# T02_LED_Cube.net
KiCad netlist of a schematic drawn in EAGLE
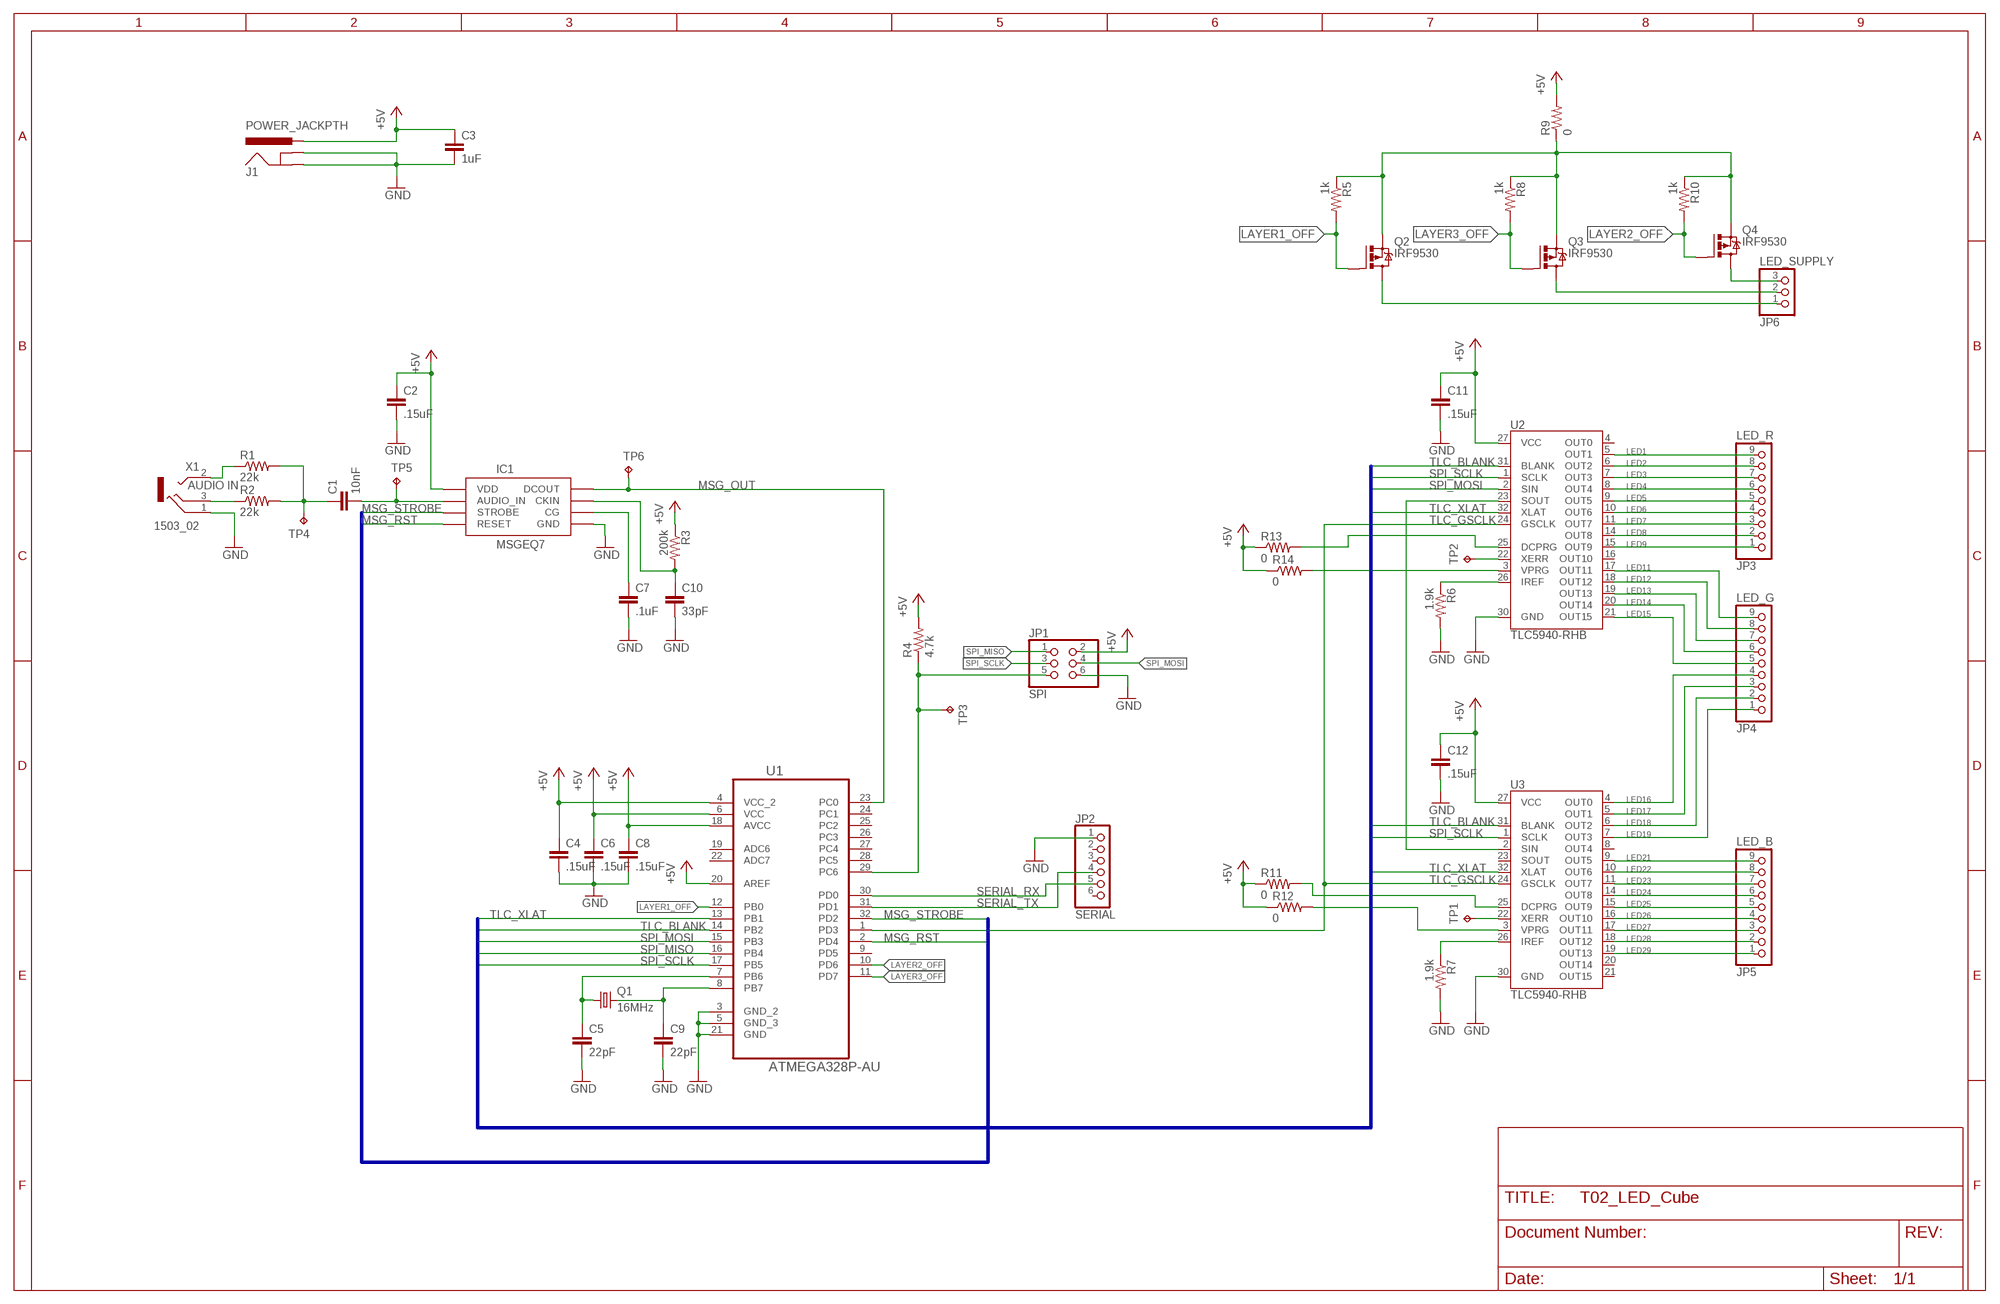
[diagram p0: schematic, sheet 1]

(export (version "E")
  (design (tool "Eeschema 10.0.6"))
  (components
    (comp (ref "C1")
      (value "10nF")
      (footprint "eagle-import:C0805")
      (libsource (lib "eagle-import") (part "C-EUC0805"))
    )
    (comp (ref "C2")
      (value ".15uF")
      (footprint "eagle-import:C0402")
      (libsource (lib "eagle-import") (part "C-EUC0402"))
    )
    (comp (ref "C3")
      (value "1uF")
      (footprint "eagle-import:C0805")
      (libsource (lib "eagle-import") (part "C-EUC0805"))
    )
    (comp (ref "C4")
      (value ".15uF")
      (footprint "eagle-import:C0402")
      (libsource (lib "eagle-import") (part "C-EUC0402"))
    )
    (comp (ref "C5")
      (value "22pF")
      (footprint "eagle-import:C0805")
      (libsource (lib "eagle-import") (part "C-EUC0805"))
    )
    (comp (ref "C6")
      (value ".15uF")
      (footprint "eagle-import:C0402")
      (libsource (lib "eagle-import") (part "C-EUC0402"))
    )
    (comp (ref "C7")
      (value ".1uF")
      (footprint "eagle-import:C0805")
      (libsource (lib "eagle-import") (part "C-EUC0805"))
    )
    (comp (ref "C8")
      (value ".15uF")
      (footprint "eagle-import:C0402")
      (libsource (lib "eagle-import") (part "C-EUC0402"))
    )
    (comp (ref "C9")
      (value "22pF")
      (footprint "eagle-import:C0805")
      (libsource (lib "eagle-import") (part "C-EUC0805"))
    )
    (comp (ref "C10")
      (value "33pF")
      (footprint "eagle-import:C0805")
      (libsource (lib "eagle-import") (part "C-EUC0805"))
    )
    (comp (ref "C11")
      (value ".15uF")
      (footprint "eagle-import:C0402")
      (libsource (lib "eagle-import") (part "C-EUC0402"))
    )
    (comp (ref "C12")
      (value ".15uF")
      (footprint "eagle-import:C0402")
      (libsource (lib "eagle-import") (part "C-EUC0402"))
    )
    (comp (ref "IC1")
      (value "MSGEQ7SOIC")
      (footprint "eagle-import:SOIC8")
      (libsource (lib "eagle-import") (part "MSGEQ7SOIC"))
    )
    (comp (ref "J1")
      (value "POWER_JACKPTH")
      (footprint "eagle-import:POWER_JACK_PTH")
      (libsource (lib "eagle-import") (part "POWER_JACKPTH"))
    )
    (comp (ref "JP1")
      (value "SPI")
      (footprint "eagle-import:2X03")
      (libsource (lib "eagle-import") (part "PINHD-2X3"))
    )
    (comp (ref "JP2")
      (value "SERIAL")
      (footprint "eagle-import:1X06")
      (libsource (lib "eagle-import") (part "PINHD-1X6"))
    )
    (comp (ref "JP3")
      (value "LED_R")
      (footprint "eagle-import:1X09")
      (libsource (lib "eagle-import") (part "PINHD-1X9"))
    )
    (comp (ref "JP4")
      (value "LED_G")
      (footprint "eagle-import:1X09")
      (libsource (lib "eagle-import") (part "PINHD-1X9"))
    )
    (comp (ref "JP5")
      (value "LED_B")
      (footprint "eagle-import:1X09")
      (libsource (lib "eagle-import") (part "PINHD-1X9"))
    )
    (comp (ref "JP6")
      (value "LED_SUPPLY")
      (footprint "eagle-import:1X03")
      (libsource (lib "eagle-import") (part "PINHD-1X3"))
    )
    (comp (ref "Q1")
      (value "16MHz")
      (footprint "eagle-import:HC49UP")
      (libsource (lib "eagle-import") (part "CRYSTALHC49UP"))
    )
    (comp (ref "Q2")
      (value "IRF9530")
      (footprint "eagle-import:TO220BV")
      (libsource (lib "eagle-import") (part "IRF9530"))
    )
    (comp (ref "Q3")
      (value "IRF9530")
      (footprint "eagle-import:TO220BV")
      (libsource (lib "eagle-import") (part "IRF9530"))
    )
    (comp (ref "Q4")
      (value "IRF9530")
      (footprint "eagle-import:TO220BV")
      (libsource (lib "eagle-import") (part "IRF9530"))
    )
    (comp (ref "R1")
      (value "22k")
      (footprint "eagle-import:R0805")
      (libsource (lib "eagle-import") (part "R-US_R0805"))
    )
    (comp (ref "R2")
      (value "22k")
      (footprint "eagle-import:R0805")
      (libsource (lib "eagle-import") (part "R-US_R0805"))
    )
    (comp (ref "R3")
      (value "200k")
      (footprint "eagle-import:R0805")
      (libsource (lib "eagle-import") (part "R-US_R0805"))
    )
    (comp (ref "R4")
      (value "4.7k")
      (footprint "eagle-import:R0805")
      (libsource (lib "eagle-import") (part "R-US_R0805"))
    )
    (comp (ref "R5")
      (value "1k")
      (footprint "eagle-import:R0805")
      (libsource (lib "eagle-import") (part "R-US_R0805"))
    )
    (comp (ref "R6")
      (value "1.9k")
      (footprint "eagle-import:R0402")
      (libsource (lib "eagle-import") (part "R-US_R0402"))
    )
    (comp (ref "R7")
      (value "1.9k")
      (footprint "eagle-import:R0402")
      (libsource (lib "eagle-import") (part "R-US_R0402"))
    )
    (comp (ref "R8")
      (value "1k")
      (footprint "eagle-import:R0805")
      (libsource (lib "eagle-import") (part "R-US_R0805"))
    )
    (comp (ref "R9")
      (value "0")
      (footprint "eagle-import:R1210")
      (libsource (lib "eagle-import") (part "R-US_R1210"))
    )
    (comp (ref "R10")
      (value "1k")
      (footprint "eagle-import:R0805")
      (libsource (lib "eagle-import") (part "R-US_R0805"))
    )
    (comp (ref "R11")
      (value "0")
      (footprint "eagle-import:R0402")
      (libsource (lib "eagle-import") (part "R-US_R0402"))
    )
    (comp (ref "R12")
      (value "0")
      (footprint "eagle-import:R0402")
      (libsource (lib "eagle-import") (part "R-US_R0402"))
    )
    (comp (ref "R13")
      (value "0")
      (footprint "eagle-import:R0402")
      (libsource (lib "eagle-import") (part "R-US_R0402"))
    )
    (comp (ref "R14")
      (value "0")
      (footprint "eagle-import:R0402")
      (libsource (lib "eagle-import") (part "R-US_R0402"))
    )
    (comp (ref "TP1")
      (value "TPPAD1-13")
      (footprint "eagle-import:P1-13")
      (libsource (lib "eagle-import") (part "TPPAD1-13"))
    )
    (comp (ref "TP2")
      (value "TPPAD1-13")
      (footprint "eagle-import:P1-13")
      (libsource (lib "eagle-import") (part "TPPAD1-13"))
    )
    (comp (ref "TP3")
      (value "TPPAD1-13")
      (footprint "eagle-import:P1-13")
      (libsource (lib "eagle-import") (part "TPPAD1-13"))
    )
    (comp (ref "TP4")
      (value "TPPAD1-13")
      (footprint "eagle-import:P1-13")
      (libsource (lib "eagle-import") (part "TPPAD1-13"))
    )
    (comp (ref "TP5")
      (value "TPPAD1-13")
      (footprint "eagle-import:P1-13")
      (libsource (lib "eagle-import") (part "TPPAD1-13"))
    )
    (comp (ref "TP6")
      (value "TPPAD1-13")
      (footprint "eagle-import:P1-13")
      (libsource (lib "eagle-import") (part "TPPAD1-13"))
    )
    (comp (ref "U1")
      (value "ATMEGA328P-AU")
      (footprint "eagle-import:QFP80P900X900X120-32N")
      (libsource (lib "eagle-import") (part "ATMEGA328P-AU"))
    )
    (comp (ref "U2")
      (value "TLC5940-RHB")
      (footprint "eagle-import:QFN-32")
      (libsource (lib "eagle-import") (part "TLC5940-RHB"))
    )
    (comp (ref "U3")
      (value "TLC5940-RHB")
      (footprint "eagle-import:QFN-32")
      (libsource (lib "eagle-import") (part "TLC5940-RHB"))
    )
    (comp (ref "X1")
      (value "1503_02")
      (footprint "eagle-import:1503_02")
      (libsource (lib "eagle-import") (part "1503_02"))
    )
  )
  (nets
    (net (code "1") (name "+5V") (class "Default")
      (node (ref "C11") (pin "1") (pinfunction "1_1") (pintype "passive"))
      (node (ref "C12") (pin "1") (pinfunction "1_1") (pintype "passive"))
      (node (ref "C2") (pin "1") (pinfunction "1_1") (pintype "passive"))
      (node (ref "C3") (pin "1") (pinfunction "1_1") (pintype "passive"))
      (node (ref "C4") (pin "1") (pinfunction "1_1") (pintype "passive"))
      (node (ref "C6") (pin "1") (pinfunction "1_1") (pintype "passive"))
      (node (ref "C8") (pin "1") (pinfunction "1_1") (pintype "passive"))
      (node (ref "IC1") (pin "1") (pinfunction "VDD_1") (pintype "input"))
      (node (ref "J1") (pin "PWR") (pinfunction "PWR_PWR") (pintype "bidirectional"))
      (node (ref "JP1") (pin "2") (pinfunction "2_2") (pintype "passive"))
      (node (ref "R11") (pin "1") (pinfunction "1_1") (pintype "passive"))
      (node (ref "R12") (pin "1") (pinfunction "1_1") (pintype "passive"))
      (node (ref "R13") (pin "1") (pinfunction "1_1") (pintype "passive"))
      (node (ref "R14") (pin "1") (pinfunction "1_1") (pintype "passive"))
      (node (ref "R3") (pin "1") (pinfunction "1_1") (pintype "passive"))
      (node (ref "R4") (pin "2") (pinfunction "2_2") (pintype "passive"))
      (node (ref "R9") (pin "2") (pinfunction "2_2") (pintype "passive"))
      (node (ref "U1") (pin "18") (pinfunction "AVCC_18") (pintype "power_in"))
      (node (ref "U1") (pin "20") (pinfunction "AREF_20") (pintype "input"))
      (node (ref "U1") (pin "4") (pinfunction "VCC_2_4") (pintype "power_in"))
      (node (ref "U1") (pin "6") (pinfunction "VCC_6") (pintype "power_in"))
      (node (ref "U2") (pin "27") (pinfunction "VCC_27") (pintype "bidirectional"))
      (node (ref "U3") (pin "27") (pinfunction "VCC_27") (pintype "bidirectional"))
    )
    (net (code "2") (name "/LED1") (class "Default")
      (node (ref "JP3") (pin "9") (pinfunction "9_9") (pintype "passive"))
      (node (ref "U2") (pin "5") (pinfunction "OUT1_5") (pintype "bidirectional"))
    )
    (net (code "3") (name "/LED2") (class "Default")
      (node (ref "JP3") (pin "8") (pinfunction "8_8") (pintype "passive"))
      (node (ref "U2") (pin "6") (pinfunction "OUT2_6") (pintype "bidirectional"))
    )
    (net (code "4") (name "/LED3") (class "Default")
      (node (ref "JP3") (pin "7") (pinfunction "7_7") (pintype "passive"))
      (node (ref "U2") (pin "7") (pinfunction "OUT3_7") (pintype "bidirectional"))
    )
    (net (code "5") (name "/LED4") (class "Default")
      (node (ref "JP3") (pin "6") (pinfunction "6_6") (pintype "passive"))
      (node (ref "U2") (pin "8") (pinfunction "OUT4_8") (pintype "bidirectional"))
    )
    (net (code "6") (name "/LED5") (class "Default")
      (node (ref "JP3") (pin "5") (pinfunction "5_5") (pintype "passive"))
      (node (ref "U2") (pin "9") (pinfunction "OUT5_9") (pintype "bidirectional"))
    )
    (net (code "7") (name "/LED6") (class "Default")
      (node (ref "JP3") (pin "4") (pinfunction "4_4") (pintype "passive"))
      (node (ref "U2") (pin "10") (pinfunction "OUT6_10") (pintype "bidirectional"))
    )
    (net (code "8") (name "/LED7") (class "Default")
      (node (ref "JP3") (pin "3") (pinfunction "3_3") (pintype "passive"))
      (node (ref "U2") (pin "11") (pinfunction "OUT7_11") (pintype "bidirectional"))
    )
    (net (code "9") (name "/LED8") (class "Default")
      (node (ref "JP3") (pin "2") (pinfunction "2_2") (pintype "passive"))
      (node (ref "U2") (pin "14") (pinfunction "OUT8_14") (pintype "bidirectional"))
    )
    (net (code "10") (name "/LED9") (class "Default")
      (node (ref "JP3") (pin "1") (pinfunction "1_1") (pintype "passive"))
      (node (ref "U2") (pin "15") (pinfunction "OUT9_15") (pintype "bidirectional"))
    )
    (net (code "11") (name "/LED11") (class "Default")
      (node (ref "JP4") (pin "9") (pinfunction "9_9") (pintype "passive"))
      (node (ref "U2") (pin "17") (pinfunction "OUT11_17") (pintype "bidirectional"))
    )
    (net (code "12") (name "/LED12") (class "Default")
      (node (ref "JP4") (pin "8") (pinfunction "8_8") (pintype "passive"))
      (node (ref "U2") (pin "18") (pinfunction "OUT12_18") (pintype "bidirectional"))
    )
    (net (code "13") (name "/LED13") (class "Default")
      (node (ref "JP4") (pin "7") (pinfunction "7_7") (pintype "passive"))
      (node (ref "U2") (pin "19") (pinfunction "OUT13_19") (pintype "bidirectional"))
    )
    (net (code "14") (name "/LED14") (class "Default")
      (node (ref "JP4") (pin "6") (pinfunction "6_6") (pintype "passive"))
      (node (ref "U2") (pin "20") (pinfunction "OUT14_20") (pintype "bidirectional"))
    )
    (net (code "15") (name "/LED15") (class "Default")
      (node (ref "JP4") (pin "5") (pinfunction "5_5") (pintype "passive"))
      (node (ref "U2") (pin "21") (pinfunction "OUT15_21") (pintype "bidirectional"))
    )
    (net (code "16") (name "/LED16") (class "Default")
      (node (ref "JP4") (pin "4") (pinfunction "4_4") (pintype "passive"))
      (node (ref "U3") (pin "4") (pinfunction "OUT0_4") (pintype "bidirectional"))
    )
    (net (code "17") (name "/LED17") (class "Default")
      (node (ref "JP4") (pin "3") (pinfunction "3_3") (pintype "passive"))
      (node (ref "U3") (pin "5") (pinfunction "OUT1_5") (pintype "bidirectional"))
    )
    (net (code "18") (name "/LED18") (class "Default")
      (node (ref "JP4") (pin "2") (pinfunction "2_2") (pintype "passive"))
      (node (ref "U3") (pin "6") (pinfunction "OUT2_6") (pintype "bidirectional"))
    )
    (net (code "19") (name "/LED19") (class "Default")
      (node (ref "JP4") (pin "1") (pinfunction "1_1") (pintype "passive"))
      (node (ref "U3") (pin "7") (pinfunction "OUT3_7") (pintype "bidirectional"))
    )
    (net (code "20") (name "/LED21") (class "Default")
      (node (ref "JP5") (pin "9") (pinfunction "9_9") (pintype "passive"))
      (node (ref "U3") (pin "9") (pinfunction "OUT5_9") (pintype "bidirectional"))
    )
    (net (code "21") (name "/LED22") (class "Default")
      (node (ref "JP5") (pin "8") (pinfunction "8_8") (pintype "passive"))
      (node (ref "U3") (pin "10") (pinfunction "OUT6_10") (pintype "bidirectional"))
    )
    (net (code "22") (name "/LED23") (class "Default")
      (node (ref "JP5") (pin "7") (pinfunction "7_7") (pintype "passive"))
      (node (ref "U3") (pin "11") (pinfunction "OUT7_11") (pintype "bidirectional"))
    )
    (net (code "23") (name "/LED24") (class "Default")
      (node (ref "JP5") (pin "6") (pinfunction "6_6") (pintype "passive"))
      (node (ref "U3") (pin "14") (pinfunction "OUT8_14") (pintype "bidirectional"))
    )
    (net (code "24") (name "/LED25") (class "Default")
      (node (ref "JP5") (pin "5") (pinfunction "5_5") (pintype "passive"))
      (node (ref "U3") (pin "15") (pinfunction "OUT9_15") (pintype "bidirectional"))
    )
    (net (code "25") (name "/LED26") (class "Default")
      (node (ref "JP5") (pin "4") (pinfunction "4_4") (pintype "passive"))
      (node (ref "U3") (pin "16") (pinfunction "OUT10_16") (pintype "bidirectional"))
    )
    (net (code "26") (name "/LED27") (class "Default")
      (node (ref "JP5") (pin "3") (pinfunction "3_3") (pintype "passive"))
      (node (ref "U3") (pin "17") (pinfunction "OUT11_17") (pintype "bidirectional"))
    )
    (net (code "27") (name "/LED28") (class "Default")
      (node (ref "JP5") (pin "2") (pinfunction "2_2") (pintype "passive"))
      (node (ref "U3") (pin "18") (pinfunction "OUT12_18") (pintype "bidirectional"))
    )
    (net (code "28") (name "/LED29") (class "Default")
      (node (ref "JP5") (pin "1") (pinfunction "1_1") (pintype "passive"))
      (node (ref "U3") (pin "19") (pinfunction "OUT13_19") (pintype "bidirectional"))
    )
    (net (code "29") (name "/MSG_OUT") (class "Default")
      (node (ref "IC1") (pin "3") (pinfunction "DCOUT_3") (pintype "bidirectional"))
      (node (ref "TP6") (pin "TP") (pinfunction "TP_TP") (pintype "input"))
      (node (ref "U1") (pin "23") (pinfunction "PC0_23") (pintype "bidirectional"))
    )
    (net (code "30") (name "/MSG_RST") (class "Default")
      (node (ref "IC1") (pin "7") (pinfunction "RESET_7") (pintype "input"))
      (node (ref "U1") (pin "2") (pinfunction "PD4_2") (pintype "bidirectional"))
    )
    (net (code "31") (name "/MSG_STROBE") (class "Default")
      (node (ref "IC1") (pin "4") (pinfunction "STROBE_4") (pintype "input"))
      (node (ref "U1") (pin "32") (pinfunction "PD2_32") (pintype "bidirectional"))
    )
    (net (code "32") (name "/SERIAL_RX") (class "Default")
      (node (ref "JP2") (pin "5") (pinfunction "5_5") (pintype "passive"))
      (node (ref "U1") (pin "30") (pinfunction "PD0_30") (pintype "bidirectional"))
    )
    (net (code "33") (name "/SERIAL_TX") (class "Default")
      (node (ref "JP2") (pin "4") (pinfunction "4_4") (pintype "passive"))
      (node (ref "U1") (pin "31") (pinfunction "PD1_31") (pintype "bidirectional"))
    )
    (net (code "34") (name "/TLC_BLANK") (class "Default")
      (node (ref "U1") (pin "14") (pinfunction "PB2_14") (pintype "bidirectional"))
      (node (ref "U2") (pin "31") (pinfunction "BLANK_31") (pintype "bidirectional"))
      (node (ref "U3") (pin "31") (pinfunction "BLANK_31") (pintype "bidirectional"))
    )
    (net (code "35") (name "/TLC_GSCLK") (class "Default")
      (node (ref "U1") (pin "1") (pinfunction "PD3_1") (pintype "bidirectional"))
      (node (ref "U2") (pin "24") (pinfunction "GSCLK_24") (pintype "bidirectional"))
      (node (ref "U3") (pin "24") (pinfunction "GSCLK_24") (pintype "bidirectional"))
    )
    (net (code "36") (name "/TLC_XLAT") (class "Default")
      (node (ref "U1") (pin "13") (pinfunction "PB1_13") (pintype "bidirectional"))
      (node (ref "U2") (pin "32") (pinfunction "XLAT_32") (pintype "bidirectional"))
      (node (ref "U3") (pin "32") (pinfunction "XLAT_32") (pintype "bidirectional"))
    )
    (net (code "37") (name "GND") (class "Default")
      (node (ref "C10") (pin "2") (pinfunction "2_2") (pintype "passive"))
      (node (ref "C11") (pin "2") (pinfunction "2_2") (pintype "passive"))
      (node (ref "C12") (pin "2") (pinfunction "2_2") (pintype "passive"))
      (node (ref "C2") (pin "2") (pinfunction "2_2") (pintype "passive"))
      (node (ref "C3") (pin "2") (pinfunction "2_2") (pintype "passive"))
      (node (ref "C4") (pin "2") (pinfunction "2_2") (pintype "passive"))
      (node (ref "C5") (pin "2") (pinfunction "2_2") (pintype "passive"))
      (node (ref "C6") (pin "2") (pinfunction "2_2") (pintype "passive"))
      (node (ref "C7") (pin "2") (pinfunction "2_2") (pintype "passive"))
      (node (ref "C8") (pin "2") (pinfunction "2_2") (pintype "passive"))
      (node (ref "C9") (pin "2") (pinfunction "2_2") (pintype "passive"))
      (node (ref "IC1") (pin "2") (pinfunction "GND_2") (pintype "bidirectional"))
      (node (ref "J1") (pin "GND") (pinfunction "GND_GND") (pintype "bidirectional"))
      (node (ref "J1") (pin "GNDBREAK") (pinfunction "GNDBREAK_GNDBREAK") (pintype "bidirectional"))
      (node (ref "JP1") (pin "6") (pinfunction "6_6") (pintype "passive"))
      (node (ref "JP2") (pin "1") (pinfunction "1_1") (pintype "passive"))
      (node (ref "R6") (pin "2") (pinfunction "2_2") (pintype "passive"))
      (node (ref "R7") (pin "2") (pinfunction "2_2") (pintype "passive"))
      (node (ref "U1") (pin "21") (pinfunction "GND_21") (pintype "passive"))
      (node (ref "U1") (pin "3") (pinfunction "GND_2_3") (pintype "passive"))
      (node (ref "U1") (pin "5") (pinfunction "GND_3_5") (pintype "passive"))
      (node (ref "U2") (pin "30") (pinfunction "GND_30") (pintype "bidirectional"))
      (node (ref "U3") (pin "30") (pinfunction "GND_30") (pintype "bidirectional"))
      (node (ref "X1") (pin "1") (pinfunction "1_1") (pintype "passive"))
    )
    (net (code "38") (name "LAYER1_OFF") (class "Default")
      (node (ref "Q2") (pin "G") (pinfunction "G_G") (pintype "passive"))
      (node (ref "R5") (pin "2") (pinfunction "2_2") (pintype "passive"))
      (node (ref "U1") (pin "12") (pinfunction "PB0_12") (pintype "bidirectional"))
    )
    (net (code "39") (name "LAYER2_OFF") (class "Default")
      (node (ref "Q4") (pin "G") (pinfunction "G_G") (pintype "passive"))
      (node (ref "R10") (pin "2") (pinfunction "2_2") (pintype "passive"))
      (node (ref "U1") (pin "10") (pinfunction "PD6_10") (pintype "bidirectional"))
    )
    (net (code "40") (name "LAYER3_OFF") (class "Default")
      (node (ref "Q3") (pin "G") (pinfunction "G_G") (pintype "passive"))
      (node (ref "R8") (pin "2") (pinfunction "2_2") (pintype "passive"))
      (node (ref "U1") (pin "11") (pinfunction "PD7_11") (pintype "bidirectional"))
    )
    (net (code "41") (name "Net-(C1-Pad1)") (class "Default")
      (node (ref "C1") (pin "1") (pinfunction "1_1") (pintype "passive"))
      (node (ref "R1") (pin "2") (pinfunction "2_2") (pintype "passive"))
      (node (ref "R2") (pin "2") (pinfunction "2_2") (pintype "passive"))
      (node (ref "TP4") (pin "TP") (pinfunction "TP_TP") (pintype "input"))
    )
    (net (code "42") (name "Net-(IC1-AUDIO_IN)") (class "Default")
      (node (ref "C1") (pin "2") (pinfunction "2_2") (pintype "passive"))
      (node (ref "IC1") (pin "5") (pinfunction "AUDIO_IN_5") (pintype "input"))
      (node (ref "TP5") (pin "TP") (pinfunction "TP_TP") (pintype "input"))
    )
    (net (code "43") (name "Net-(IC1-CG)") (class "Default")
      (node (ref "C7") (pin "1") (pinfunction "1_1") (pintype "passive"))
      (node (ref "IC1") (pin "6") (pinfunction "CG_6") (pintype "bidirectional"))
    )
    (net (code "44") (name "Net-(IC1-CKIN)") (class "Default")
      (node (ref "C10") (pin "1") (pinfunction "1_1") (pintype "passive"))
      (node (ref "IC1") (pin "8") (pinfunction "CKIN_8") (pintype "bidirectional"))
      (node (ref "R3") (pin "2") (pinfunction "2_2") (pintype "passive"))
    )
    (net (code "45") (name "Net-(JP6-Pad1)") (class "Default")
      (node (ref "JP6") (pin "1") (pinfunction "1_1") (pintype "passive"))
      (node (ref "Q2") (pin "D") (pinfunction "D_D") (pintype "passive"))
    )
    (net (code "46") (name "Net-(JP6-Pad2)") (class "Default")
      (node (ref "JP6") (pin "2") (pinfunction "2_2") (pintype "passive"))
      (node (ref "Q3") (pin "D") (pinfunction "D_D") (pintype "passive"))
    )
    (net (code "47") (name "Net-(JP6-Pad3)") (class "Default")
      (node (ref "JP6") (pin "3") (pinfunction "3_3") (pintype "passive"))
      (node (ref "Q4") (pin "D") (pinfunction "D_D") (pintype "passive"))
    )
    (net (code "48") (name "Net-(Q2-PadS)") (class "Default")
      (node (ref "Q2") (pin "S") (pinfunction "S_S") (pintype "passive"))
      (node (ref "Q3") (pin "S") (pinfunction "S_S") (pintype "passive"))
      (node (ref "Q4") (pin "S") (pinfunction "S_S") (pintype "passive"))
      (node (ref "R10") (pin "1") (pinfunction "1_1") (pintype "passive"))
      (node (ref "R5") (pin "1") (pinfunction "1_1") (pintype "passive"))
      (node (ref "R8") (pin "1") (pinfunction "1_1") (pintype "passive"))
      (node (ref "R9") (pin "1") (pinfunction "1_1") (pintype "passive"))
    )
    (net (code "49") (name "Net-(R1-Pad1)") (class "Default")
      (node (ref "R1") (pin "1") (pinfunction "1_1") (pintype "passive"))
      (node (ref "X1") (pin "2") (pinfunction "2_2") (pintype "passive"))
    )
    (net (code "50") (name "Net-(R2-Pad1)") (class "Default")
      (node (ref "R2") (pin "1") (pinfunction "1_1") (pintype "passive"))
      (node (ref "X1") (pin "3") (pinfunction "3_3") (pintype "passive"))
    )
    (net (code "51") (name "Net-(U1-PB6)") (class "Default")
      (node (ref "C5") (pin "1") (pinfunction "1_1") (pintype "passive"))
      (node (ref "Q1") (pin "1") (pinfunction "1_1") (pintype "passive"))
      (node (ref "U1") (pin "7") (pinfunction "PB6_7") (pintype "bidirectional"))
    )
    (net (code "52") (name "Net-(U1-PB7)") (class "Default")
      (node (ref "C9") (pin "1") (pinfunction "1_1") (pintype "passive"))
      (node (ref "Q1") (pin "2") (pinfunction "2_2") (pintype "passive"))
      (node (ref "U1") (pin "8") (pinfunction "PB7_8") (pintype "bidirectional"))
    )
    (net (code "53") (name "Net-(U1-PC6)") (class "Default")
      (node (ref "JP1") (pin "5") (pinfunction "5_5") (pintype "passive"))
      (node (ref "R4") (pin "1") (pinfunction "1_1") (pintype "passive"))
      (node (ref "TP3") (pin "TP") (pinfunction "TP_TP") (pintype "input"))
      (node (ref "U1") (pin "29") (pinfunction "PC6_29") (pintype "bidirectional"))
    )
    (net (code "54") (name "Net-(U2-DCPRG)") (class "Default")
      (node (ref "R13") (pin "2") (pinfunction "2_2") (pintype "passive"))
      (node (ref "U2") (pin "25") (pinfunction "DCPRG_25") (pintype "bidirectional"))
    )
    (net (code "55") (name "Net-(U2-IREF)") (class "Default")
      (node (ref "R6") (pin "1") (pinfunction "1_1") (pintype "passive"))
      (node (ref "U2") (pin "26") (pinfunction "IREF_26") (pintype "bidirectional"))
    )
    (net (code "56") (name "Net-(U2-SOUT)") (class "Default")
      (node (ref "U2") (pin "23") (pinfunction "SOUT_23") (pintype "bidirectional"))
      (node (ref "U3") (pin "2") (pinfunction "SIN_2") (pintype "bidirectional"))
    )
    (net (code "57") (name "Net-(U2-VPRG)") (class "Default")
      (node (ref "R14") (pin "2") (pinfunction "2_2") (pintype "passive"))
      (node (ref "U2") (pin "3") (pinfunction "VPRG_3") (pintype "bidirectional"))
    )
    (net (code "58") (name "Net-(U2-XERR)") (class "Default")
      (node (ref "TP2") (pin "TP") (pinfunction "TP_TP") (pintype "input"))
      (node (ref "U2") (pin "22") (pinfunction "XERR_22") (pintype "bidirectional"))
    )
    (net (code "59") (name "Net-(U3-DCPRG)") (class "Default")
      (node (ref "R11") (pin "2") (pinfunction "2_2") (pintype "passive"))
      (node (ref "U3") (pin "25") (pinfunction "DCPRG_25") (pintype "bidirectional"))
    )
    (net (code "60") (name "Net-(U3-IREF)") (class "Default")
      (node (ref "R7") (pin "1") (pinfunction "1_1") (pintype "passive"))
      (node (ref "U3") (pin "26") (pinfunction "IREF_26") (pintype "bidirectional"))
    )
    (net (code "61") (name "Net-(U3-VPRG)") (class "Default")
      (node (ref "R12") (pin "2") (pinfunction "2_2") (pintype "passive"))
      (node (ref "U3") (pin "3") (pinfunction "VPRG_3") (pintype "bidirectional"))
    )
    (net (code "62") (name "Net-(U3-XERR)") (class "Default")
      (node (ref "TP1") (pin "TP") (pinfunction "TP_TP") (pintype "input"))
      (node (ref "U3") (pin "22") (pinfunction "XERR_22") (pintype "bidirectional"))
    )
    (net (code "63") (name "SPI_MISO") (class "Default")
      (node (ref "JP1") (pin "1") (pinfunction "1_1") (pintype "passive"))
      (node (ref "U1") (pin "16") (pinfunction "PB4_16") (pintype "bidirectional"))
    )
    (net (code "64") (name "SPI_MOSI") (class "Default")
      (node (ref "JP1") (pin "4") (pinfunction "4_4") (pintype "passive"))
      (node (ref "U1") (pin "15") (pinfunction "PB3_15") (pintype "bidirectional"))
      (node (ref "U2") (pin "2") (pinfunction "SIN_2") (pintype "bidirectional"))
    )
    (net (code "65") (name "SPI_SCLK") (class "Default")
      (node (ref "JP1") (pin "3") (pinfunction "3_3") (pintype "passive"))
      (node (ref "U1") (pin "17") (pinfunction "PB5_17") (pintype "bidirectional"))
      (node (ref "U2") (pin "1") (pinfunction "SCLK_1") (pintype "bidirectional"))
      (node (ref "U3") (pin "1") (pinfunction "SCLK_1") (pintype "bidirectional"))
    )
    (net (code "66") (name "unconnected-(JP2-Pad2)") (class "Default")
      (node (ref "JP2") (pin "2") (pinfunction "2_2") (pintype "passive"))
    )
    (net (code "67") (name "unconnected-(JP2-Pad3)") (class "Default")
      (node (ref "JP2") (pin "3") (pinfunction "3_3") (pintype "passive"))
    )
    (net (code "68") (name "unconnected-(JP2-Pad6)") (class "Default")
      (node (ref "JP2") (pin "6") (pinfunction "6_6") (pintype "passive"))
    )
    (net (code "69") (name "unconnected-(U1-ADC6-Pad19)") (class "Default")
      (node (ref "U1") (pin "19") (pinfunction "ADC6_19") (pintype "input"))
    )
    (net (code "70") (name "unconnected-(U1-ADC7-Pad22)") (class "Default")
      (node (ref "U1") (pin "22") (pinfunction "ADC7_22") (pintype "input"))
    )
    (net (code "71") (name "unconnected-(U1-PC1-Pad24)") (class "Default")
      (node (ref "U1") (pin "24") (pinfunction "PC1_24") (pintype "bidirectional"))
    )
    (net (code "72") (name "unconnected-(U1-PC2-Pad25)") (class "Default")
      (node (ref "U1") (pin "25") (pinfunction "PC2_25") (pintype "bidirectional"))
    )
    (net (code "73") (name "unconnected-(U1-PC3-Pad26)") (class "Default")
      (node (ref "U1") (pin "26") (pinfunction "PC3_26") (pintype "bidirectional"))
    )
    (net (code "74") (name "unconnected-(U1-PC4-Pad27)") (class "Default")
      (node (ref "U1") (pin "27") (pinfunction "PC4_27") (pintype "bidirectional"))
    )
    (net (code "75") (name "unconnected-(U1-PC5-Pad28)") (class "Default")
      (node (ref "U1") (pin "28") (pinfunction "PC5_28") (pintype "bidirectional"))
    )
    (net (code "76") (name "unconnected-(U1-PD5-Pad9)") (class "Default")
      (node (ref "U1") (pin "9") (pinfunction "PD5_9") (pintype "bidirectional"))
    )
    (net (code "77") (name "unconnected-(U2-OUT0-Pad4)") (class "Default")
      (node (ref "U2") (pin "4") (pinfunction "OUT0_4") (pintype "bidirectional"))
    )
    (net (code "78") (name "unconnected-(U2-OUT10-Pad16)") (class "Default")
      (node (ref "U2") (pin "16") (pinfunction "OUT10_16") (pintype "bidirectional"))
    )
    (net (code "79") (name "unconnected-(U3-OUT4-Pad8)") (class "Default")
      (node (ref "U3") (pin "8") (pinfunction "OUT4_8") (pintype "bidirectional"))
    )
    (net (code "80") (name "unconnected-(U3-OUT14-Pad20)") (class "Default")
      (node (ref "U3") (pin "20") (pinfunction "OUT14_20") (pintype "bidirectional"))
    )
    (net (code "81") (name "unconnected-(U3-OUT15-Pad21)") (class "Default")
      (node (ref "U3") (pin "21") (pinfunction "OUT15_21") (pintype "bidirectional"))
    )
    (net (code "82") (name "unconnected-(U3-SOUT-Pad23)") (class "Default")
      (node (ref "U3") (pin "23") (pinfunction "SOUT_23") (pintype "bidirectional"))
    )
    (net (code "83") (name "unconnected-(X1-2-Pad2@2)") (class "Default")
      (node (ref "X1") (pin "2@2") (pinfunction "2_2@2") (pintype "passive"))
    )
  )
)
